# Input_PC.net
KiCad netlist of a schematic drawn in Altium Designer
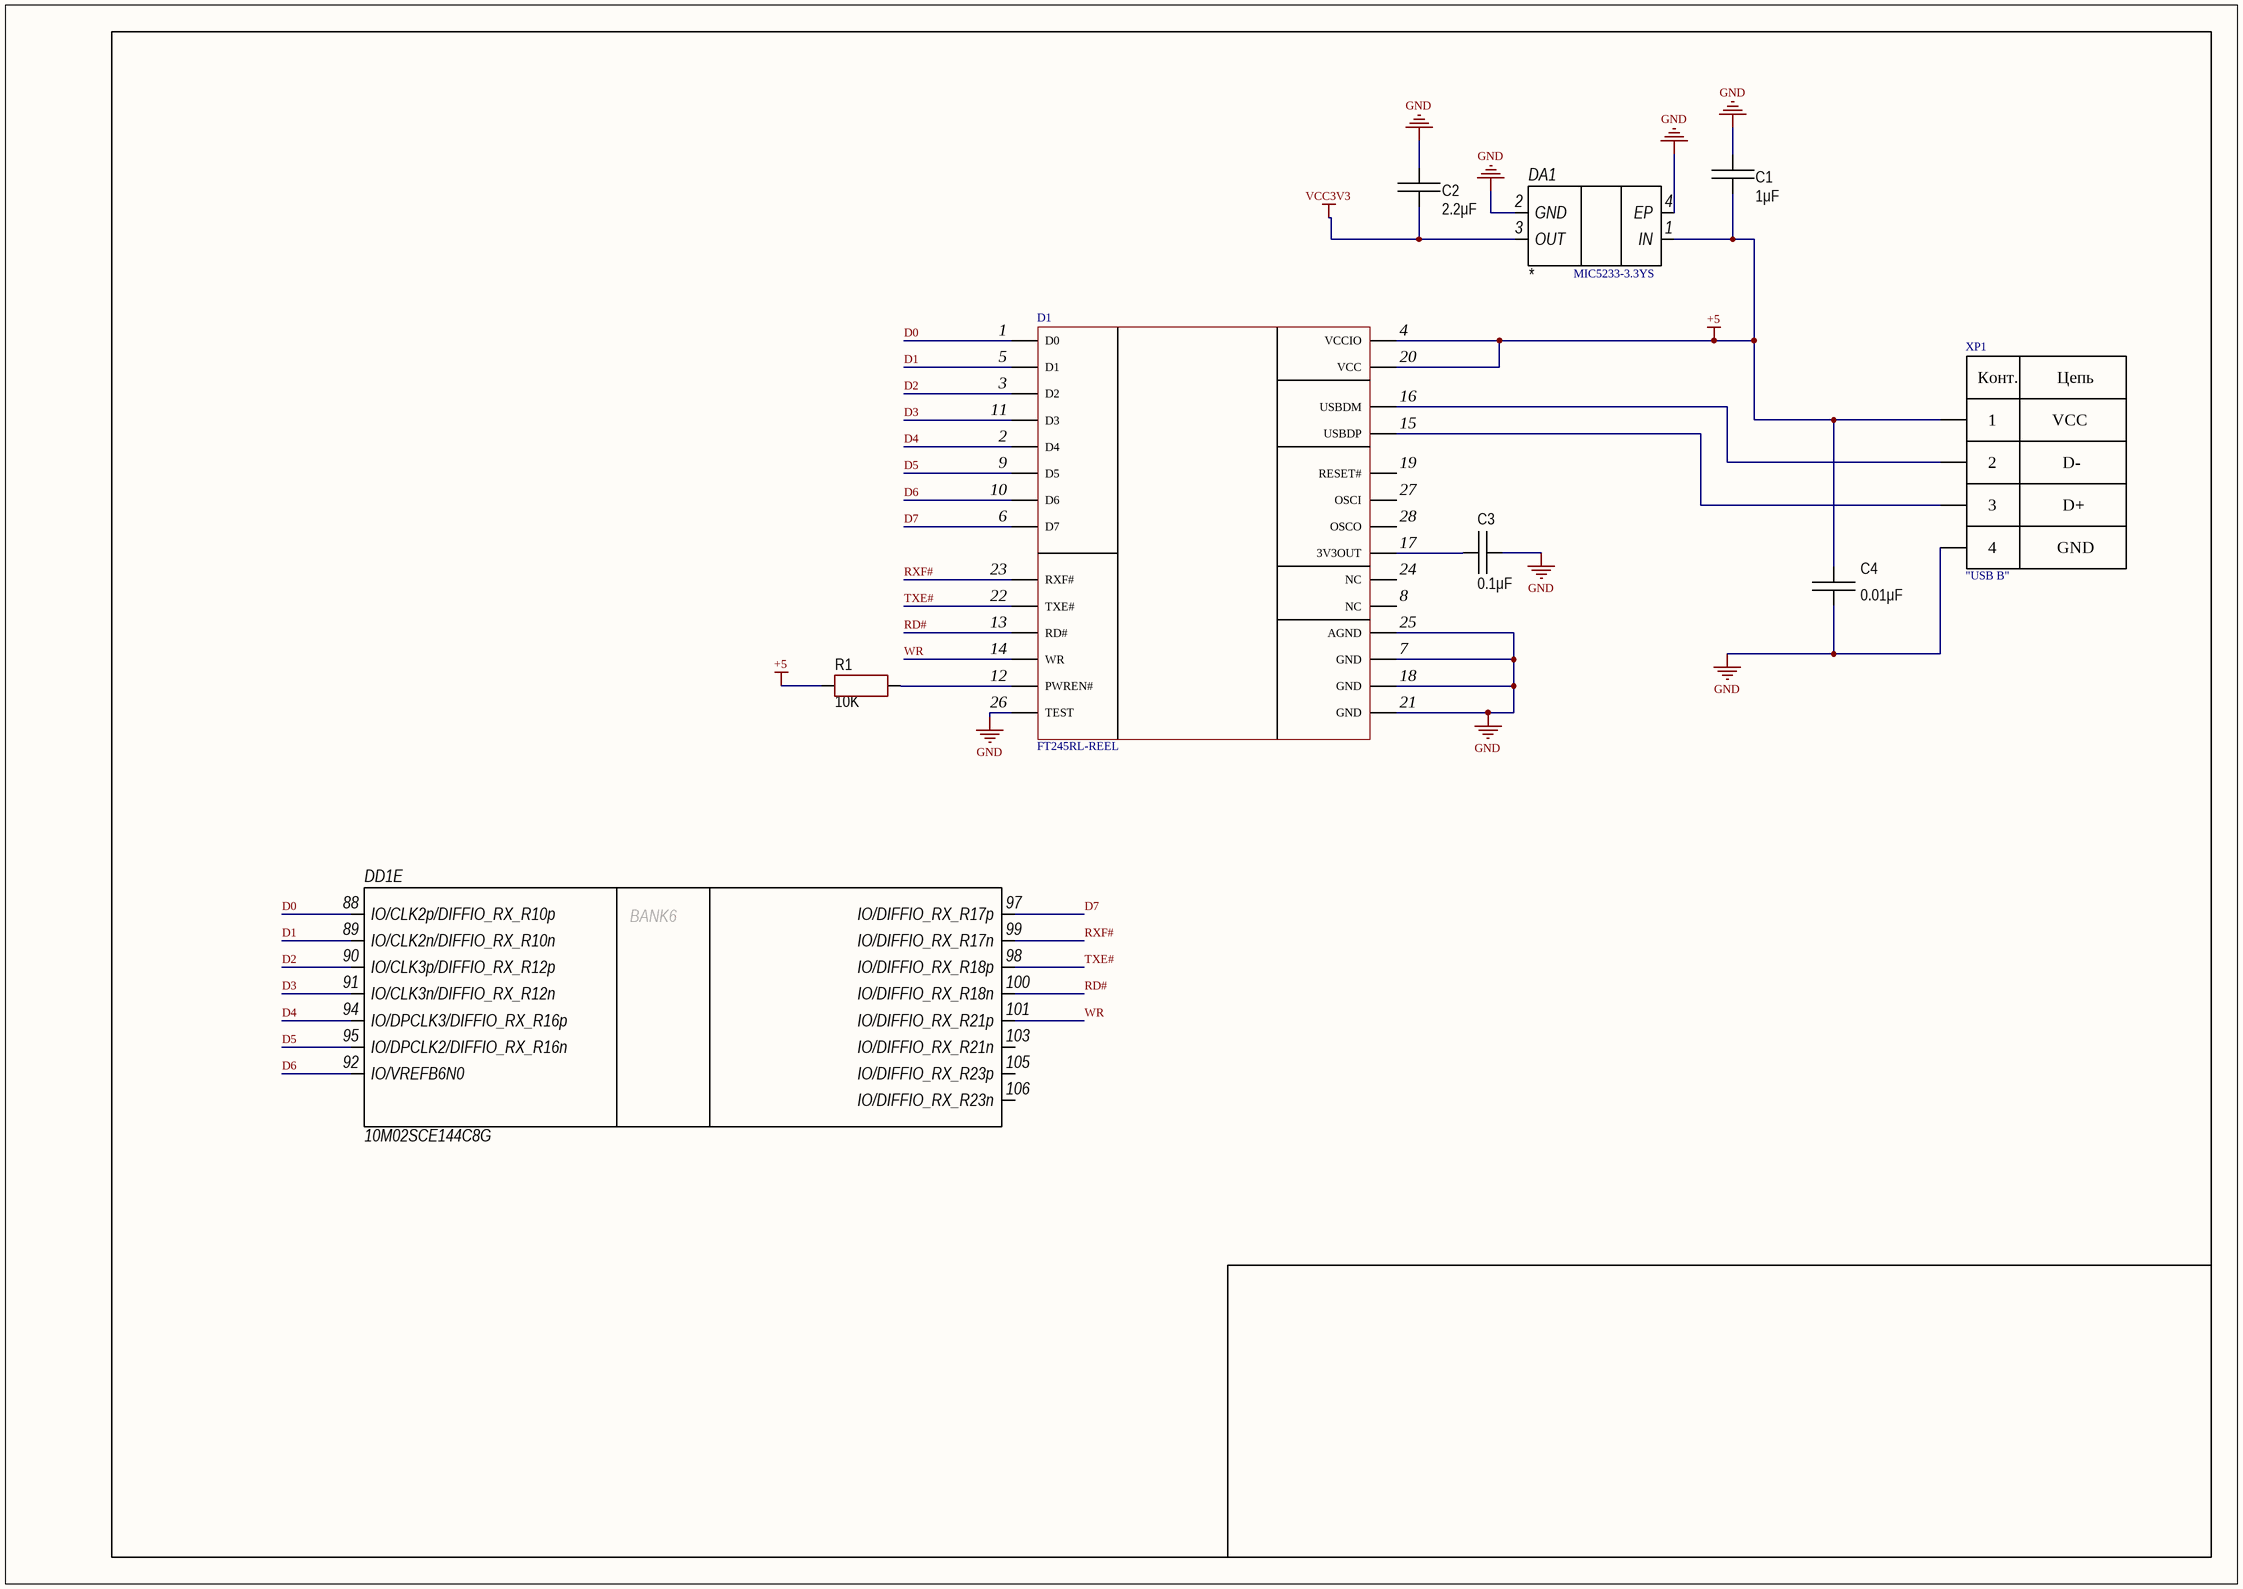
[diagram p0: Input_PC.SchDoc]

(export (version "E")
  (design (tool "Eeschema 10.0.6"))
  (components
    (comp (ref "C1")
      (value "1μF")
      (footprint "CAP: 0805")
      (fields (field (name "VALUEMANUFACTURERPARTNUMBER") "Ceramic capacitor, 1μF, X7R, , , 0805, "))
      (libsource (lib "Capacitor") (part "Ceramic_0805"))
    )
    (comp (ref "C2")
      (value "2.2μF")
      (footprint "CAP: 0805")
      (fields (field (name "VALUEMANUFACTURERPARTNUMBER") "Ceramic capacitor, 2.2μF, X7R, , , 0805, "))
      (libsource (lib "Capacitor") (part "Ceramic_0805"))
    )
    (comp (ref "C3")
      (value "0.1μF")
      (footprint "CAP: 0805")
      (fields
        (field (name "MANUFACTURER") "Yageo")
        (field (name "PARTNUMBER") "CC0805KRX7R7BB104")
        (field (name "VALUEMANUFACTURERPARTNUMBER") "Ceramic capacitor, 0.1μF, X7R, ±10%, , 0805, -55...+125°C")
      )
      (libsource (lib "Capacitor") (part "Ceramic_0805"))
    )
    (comp (ref "C4")
      (value "0.01μF")
      (footprint "CAP: 0201")
      (fields
        (field (name "MANUFACTURER") "Yageo")
        (field (name "PARTNUMBER") "CC0201KRX7R7BB103")
        (field (name "VALUEMANUFACTURERPARTNUMBER") "Ceramic capacitor, 0.01μF, X7R, ±10%, 16V, 0201, -55...+125°C")
      )
      (libsource (lib "Capacitor") (part "Ceramic_0201"))
    )
    (comp (ref "D1")
      (value "FT245RL-REEL")
      (footprint "28-SSOP")
      (description "IC USB TO PARALLEL FIFO 28-SSOP")
      (libsource (lib "Integrated_Library") (part "FT245RL-REEL"))
    )
    (comp (ref "DA1")
      (value "*")
      (footprint "sot223")
      (description "Voltage Regulator")
      (fields (field (name "PARTNUMBER") "MIC5233-3.3YS"))
      (libsource (lib "Integrated_Library") (part "MIC5233"))
    )
    (comp (ref "DD1")
      (value "10M02SCE144C8G")
      (footprint "144-Lead EQFP")
      (description "MAX10 FPGA")
      (fields (field (name "MANUFACTURER") "Intel"))
      (libsource (lib "Integrated_Library") (part "10M02SCE144C8G"))
    )
    (comp (ref "R1")
      (value "10K")
      (footprint "RES: 0805")
      (fields
        (field (name "MANUFACTURER") "Yageo")
        (field (name "PARTNUMBER") "RC0805JR-07100RL")
        (field (name "VALUEMANUFACTURERPARTNUMBER") "Resistor film, 10K, , 0805, 0.125W, -55...+125°C")
      )
      (libsource (lib "Resistor") (part "Resistor_0805"))
    )
    (comp (ref "XP1")
      (value "\"USB B\"")
      (footprint "USB B")
      (libsource (lib "Integrated_Library") (part "USB B"))
    )
  )
  (nets
    (net (code "1") (name "+5") (class "Default")
      (node (ref "C1") (pin "2") (pinfunction "2_2") (pintype "power_in"))
      (node (ref "C4") (pin "2") (pinfunction "2_2") (pintype "power_in"))
      (node (ref "D1") (pin "20") (pinfunction "VCC_20") (pintype "power_in"))
      (node (ref "D1") (pin "4") (pinfunction "VCCIO_4") (pintype "power_in"))
      (node (ref "DA1") (pin "1") (pinfunction "IN_1") (pintype "power_in"))
      (node (ref "R1") (pin "1") (pinfunction "1_1") (pintype "passive"))
      (node (ref "XP1") (pin "1") (pinfunction "1_1") (pintype "passive"))
    )
    (net (code "2") (name "/D0") (class "Default")
      (node (ref "D1") (pin "1") (pinfunction "D0_1") (pintype "power_in"))
      (node (ref "DD1") (pin "88") (pinfunction "IO/CLK2p/DIFFIO_RX_R10p_88") (pintype "power_in"))
    )
    (net (code "3") (name "/D1") (class "Default")
      (node (ref "D1") (pin "5") (pinfunction "D1_5") (pintype "power_in"))
      (node (ref "DD1") (pin "89") (pinfunction "IO/CLK2n/DIFFIO_RX_R10n_89") (pintype "power_in"))
    )
    (net (code "4") (name "/D2") (class "Default")
      (node (ref "D1") (pin "3") (pinfunction "D2_3") (pintype "power_in"))
      (node (ref "DD1") (pin "90") (pinfunction "IO/CLK3p/DIFFIO_RX_R12p_90") (pintype "power_in"))
    )
    (net (code "5") (name "/D3") (class "Default")
      (node (ref "D1") (pin "11") (pinfunction "D3_11") (pintype "power_in"))
      (node (ref "DD1") (pin "91") (pinfunction "IO/CLK3n/DIFFIO_RX_R12n_91") (pintype "power_in"))
    )
    (net (code "6") (name "/D4") (class "Default")
      (node (ref "D1") (pin "2") (pinfunction "D4_2") (pintype "power_in"))
      (node (ref "DD1") (pin "94") (pinfunction "IO/DPCLK3/DIFFIO_RX_R16p_94") (pintype "power_in"))
    )
    (net (code "7") (name "/D5") (class "Default")
      (node (ref "D1") (pin "9") (pinfunction "D5_9") (pintype "power_in"))
      (node (ref "DD1") (pin "95") (pinfunction "IO/DPCLK2/DIFFIO_RX_R16n_95") (pintype "power_in"))
    )
    (net (code "8") (name "/D6") (class "Default")
      (node (ref "D1") (pin "10") (pinfunction "D6_10") (pintype "power_in"))
      (node (ref "DD1") (pin "92") (pinfunction "IO/VREFB6N0_92") (pintype "power_in"))
    )
    (net (code "9") (name "/D7") (class "Default")
      (node (ref "D1") (pin "6") (pinfunction "D7_6") (pintype "power_in"))
      (node (ref "DD1") (pin "97") (pinfunction "IO/DIFFIO_RX_R17p_97") (pintype "power_in"))
    )
    (net (code "10") (name "/RD#") (class "Default")
      (node (ref "D1") (pin "13") (pinfunction "RD#_13") (pintype "power_in"))
      (node (ref "DD1") (pin "100") (pinfunction "IO/DIFFIO_RX_R18n_100") (pintype "power_in"))
    )
    (net (code "11") (name "/RXF#") (class "Default")
      (node (ref "D1") (pin "23") (pinfunction "RXF#_23") (pintype "power_in"))
      (node (ref "DD1") (pin "99") (pinfunction "IO/DIFFIO_RX_R17n_99") (pintype "power_in"))
    )
    (net (code "12") (name "/TXE#") (class "Default")
      (node (ref "D1") (pin "22") (pinfunction "TXE#_22") (pintype "power_in"))
      (node (ref "DD1") (pin "98") (pinfunction "IO/DIFFIO_RX_R18p_98") (pintype "power_in"))
    )
    (net (code "13") (name "/WR") (class "Default")
      (node (ref "D1") (pin "14") (pinfunction "WR_14") (pintype "power_in"))
      (node (ref "DD1") (pin "101") (pinfunction "IO/DIFFIO_RX_R21p_101") (pintype "power_in"))
    )
    (net (code "14") (name "GND") (class "Default")
      (node (ref "C1") (pin "1") (pinfunction "1_1") (pintype "power_in"))
      (node (ref "C2") (pin "2") (pinfunction "2_2") (pintype "power_in"))
      (node (ref "C3") (pin "2") (pinfunction "2_2") (pintype "power_in"))
      (node (ref "C4") (pin "1") (pinfunction "1_1") (pintype "power_in"))
      (node (ref "D1") (pin "18") (pinfunction "GND_18") (pintype "power_in"))
      (node (ref "D1") (pin "21") (pinfunction "GND_21") (pintype "power_in"))
      (node (ref "D1") (pin "25") (pinfunction "AGND_25") (pintype "power_in"))
      (node (ref "D1") (pin "26") (pinfunction "TEST_26") (pintype "power_in"))
      (node (ref "D1") (pin "7") (pinfunction "GND_7") (pintype "power_in"))
      (node (ref "DA1") (pin "2") (pinfunction "GND_2") (pintype "power_in"))
      (node (ref "DA1") (pin "4") (pinfunction "EP_4") (pintype "power_in"))
      (node (ref "XP1") (pin "4") (pinfunction "4_4") (pintype "passive"))
    )
    (net (code "15") (name "Net-(D1-3V3OUT)") (class "Default")
      (node (ref "C3") (pin "1") (pinfunction "1_1") (pintype "power_in"))
      (node (ref "D1") (pin "17") (pinfunction "3V3OUT_17") (pintype "power_in"))
    )
    (net (code "16") (name "Net-(D1-PWREN#)") (class "Default")
      (node (ref "D1") (pin "12") (pinfunction "PWREN#_12") (pintype "power_in"))
      (node (ref "R1") (pin "2") (pinfunction "2_2") (pintype "passive"))
    )
    (net (code "17") (name "Net-(D1-USBDM)") (class "Default")
      (node (ref "D1") (pin "16") (pinfunction "USBDM_16") (pintype "power_in"))
      (node (ref "XP1") (pin "2") (pinfunction "2_2") (pintype "passive"))
    )
    (net (code "18") (name "Net-(D1-USBDP)") (class "Default")
      (node (ref "D1") (pin "15") (pinfunction "USBDP_15") (pintype "power_in"))
      (node (ref "XP1") (pin "3") (pinfunction "3_3") (pintype "passive"))
    )
    (net (code "19") (name "VCC3V3") (class "Default")
      (node (ref "C2") (pin "1") (pinfunction "1_1") (pintype "power_in"))
      (node (ref "DA1") (pin "3") (pinfunction "OUT_3") (pintype "power_in"))
    )
    (net (code "20") (name "unconnected-(D1-NC-Pad8)") (class "Default")
      (node (ref "D1") (pin "8") (pinfunction "NC_8") (pintype "power_in"))
    )
    (net (code "21") (name "unconnected-(D1-NC-Pad24)") (class "Default")
      (node (ref "D1") (pin "24") (pinfunction "NC_24") (pintype "power_in"))
    )
    (net (code "22") (name "unconnected-(D1-OSCI-Pad27)") (class "Default")
      (node (ref "D1") (pin "27") (pinfunction "OSCI_27") (pintype "power_in"))
    )
    (net (code "23") (name "unconnected-(D1-OSCO-Pad28)") (class "Default")
      (node (ref "D1") (pin "28") (pinfunction "OSCO_28") (pintype "power_in"))
    )
    (net (code "24") (name "unconnected-(D1-RESET#-Pad19)") (class "Default")
      (node (ref "D1") (pin "19") (pinfunction "RESET#_19") (pintype "power_in"))
    )
    (net (code "25") (name "unconnected-(DD1E-IO{slash}DIFFIO_RX_R21n-Pad103)") (class "Default")
      (node (ref "DD1") (pin "103") (pinfunction "IO/DIFFIO_RX_R21n_103") (pintype "power_in"))
    )
    (net (code "26") (name "unconnected-(DD1E-IO{slash}DIFFIO_RX_R23n-Pad106)") (class "Default")
      (node (ref "DD1") (pin "106") (pinfunction "IO/DIFFIO_RX_R23n_106") (pintype "power_in"))
    )
    (net (code "27") (name "unconnected-(DD1E-IO{slash}DIFFIO_RX_R23p-Pad105)") (class "Default")
      (node (ref "DD1") (pin "105") (pinfunction "IO/DIFFIO_RX_R23p_105") (pintype "power_in"))
    )
  )
)
